# knife.net
KiCad netlist of a schematic drawn in EAGLE
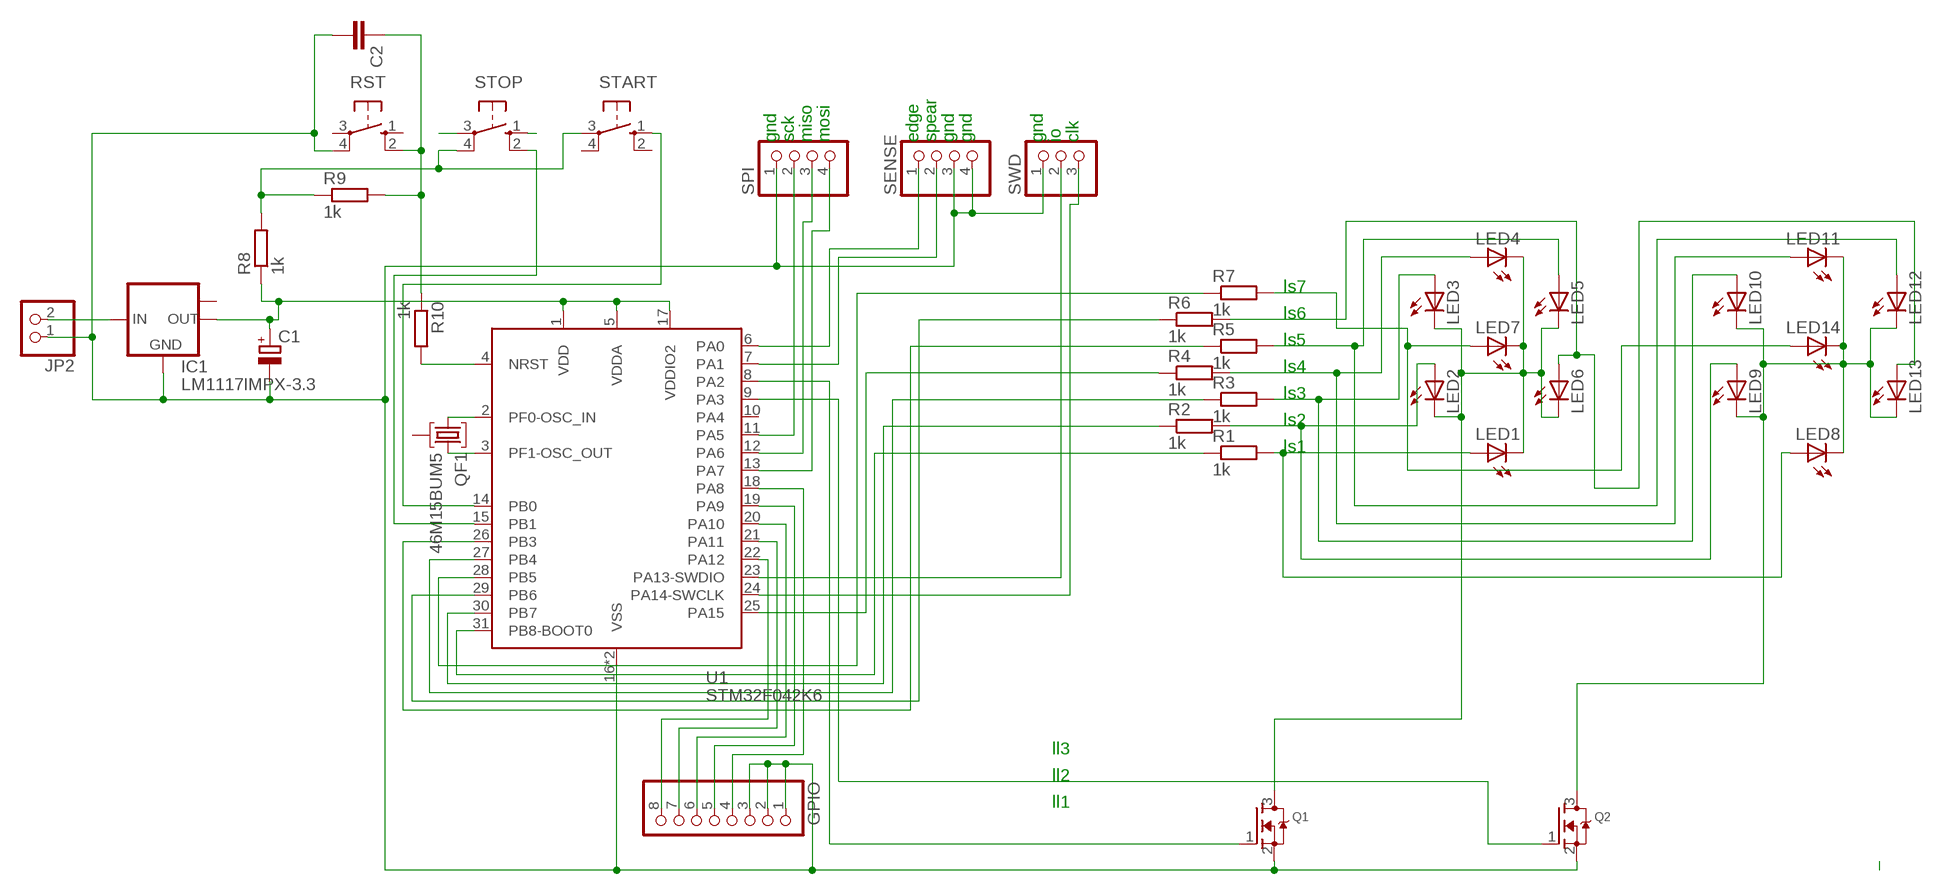
[diagram p0: schematic, sheet 1]

(export (version "E")
  (design (tool "Eeschema 10.0.6"))
  (components
    (comp (ref "C1")
      (value "CPOL-EUSMCD")
      (footprint "eagle-import:SMC_D")
      (libsource (lib "eagle-import") (part "CPOL-EUSMCD"))
    )
    (comp (ref "C2")
      (value "C-EUC1206")
      (footprint "eagle-import:C1206")
      (libsource (lib "eagle-import") (part "C-EUC1206"))
    )
    (comp (ref "GPIO")
      (value "PINHD-1X8")
      (footprint "eagle-import:1X08")
      (libsource (lib "eagle-import") (part "PINHD-1X8"))
    )
    (comp (ref "IC1")
      (value "LM1117IMPX-3.3")
      (footprint "eagle-import:SOT223")
      (libsource (lib "eagle-import") (part "LM1117IMPX-3.3"))
    )
    (comp (ref "JP2")
      (value "PINHD-1X2")
      (footprint "eagle-import:1X02")
      (libsource (lib "eagle-import") (part "PINHD-1X2"))
    )
    (comp (ref "LED1")
      (value "LEDSQR2X5")
      (footprint "eagle-import:LED2X5")
      (libsource (lib "eagle-import") (part "LEDSQR2X5"))
    )
    (comp (ref "LED2")
      (value "LEDSQR2X5")
      (footprint "eagle-import:LED2X5")
      (libsource (lib "eagle-import") (part "LEDSQR2X5"))
    )
    (comp (ref "LED3")
      (value "LEDSQR2X5")
      (footprint "eagle-import:LED2X5")
      (libsource (lib "eagle-import") (part "LEDSQR2X5"))
    )
    (comp (ref "LED4")
      (value "LEDSQR2X5")
      (footprint "eagle-import:LED2X5")
      (libsource (lib "eagle-import") (part "LEDSQR2X5"))
    )
    (comp (ref "LED5")
      (value "LEDSQR2X5")
      (footprint "eagle-import:LED2X5")
      (libsource (lib "eagle-import") (part "LEDSQR2X5"))
    )
    (comp (ref "LED6")
      (value "LEDSQR2X5")
      (footprint "eagle-import:LED2X5")
      (libsource (lib "eagle-import") (part "LEDSQR2X5"))
    )
    (comp (ref "LED7")
      (value "LEDSQR2X5")
      (footprint "eagle-import:LED2X5")
      (libsource (lib "eagle-import") (part "LEDSQR2X5"))
    )
    (comp (ref "LED8")
      (value "LEDSQR2X5")
      (footprint "eagle-import:LED2X5")
      (libsource (lib "eagle-import") (part "LEDSQR2X5"))
    )
    (comp (ref "LED9")
      (value "LEDSQR2X5")
      (footprint "eagle-import:LED2X5")
      (libsource (lib "eagle-import") (part "LEDSQR2X5"))
    )
    (comp (ref "LED10")
      (value "LEDSQR2X5")
      (footprint "eagle-import:LED2X5")
      (libsource (lib "eagle-import") (part "LEDSQR2X5"))
    )
    (comp (ref "LED11")
      (value "LEDSQR2X5")
      (footprint "eagle-import:LED2X5")
      (libsource (lib "eagle-import") (part "LEDSQR2X5"))
    )
    (comp (ref "LED12")
      (value "LEDSQR2X5")
      (footprint "eagle-import:LED2X5")
      (libsource (lib "eagle-import") (part "LEDSQR2X5"))
    )
    (comp (ref "LED13")
      (value "LEDSQR2X5")
      (footprint "eagle-import:LED2X5")
      (libsource (lib "eagle-import") (part "LEDSQR2X5"))
    )
    (comp (ref "LED14")
      (value "LEDSQR2X5")
      (footprint "eagle-import:LED2X5")
      (libsource (lib "eagle-import") (part "LEDSQR2X5"))
    )
    (comp (ref "Q1")
      (value "MOSFET-NREFLOW")
      (footprint "eagle-import:SOT23")
      (libsource (lib "eagle-import") (part "MOSFET-NREFLOW"))
    )
    (comp (ref "Q2")
      (value "MOSFET-NREFLOW")
      (footprint "eagle-import:SOT23")
      (libsource (lib "eagle-import") (part "MOSFET-NREFLOW"))
    )
    (comp (ref "QF1")
      (value "46M15BUM5")
      (footprint "eagle-import:UM5")
      (libsource (lib "eagle-import") (part "46M15BUM5"))
    )
    (comp (ref "R1")
      (value "1k")
      (footprint "eagle-import:R0805")
      (libsource (lib "eagle-import") (part "resistor_R-EU_R0805"))
    )
    (comp (ref "R2")
      (value "1k")
      (footprint "eagle-import:R0805")
      (libsource (lib "eagle-import") (part "resistor_R-EU_R0805"))
    )
    (comp (ref "R3")
      (value "1k")
      (footprint "eagle-import:R0805")
      (libsource (lib "eagle-import") (part "resistor_R-EU_R0805"))
    )
    (comp (ref "R4")
      (value "1k")
      (footprint "eagle-import:R0805")
      (libsource (lib "eagle-import") (part "resistor_R-EU_R0805"))
    )
    (comp (ref "R5")
      (value "1k")
      (footprint "eagle-import:R0805")
      (libsource (lib "eagle-import") (part "resistor_R-EU_R0805"))
    )
    (comp (ref "R6")
      (value "1k")
      (footprint "eagle-import:R0805")
      (libsource (lib "eagle-import") (part "resistor_R-EU_R0805"))
    )
    (comp (ref "R7")
      (value "1k")
      (footprint "eagle-import:R0805")
      (libsource (lib "eagle-import") (part "resistor_R-EU_R0805"))
    )
    (comp (ref "R8")
      (value "1k")
      (footprint "eagle-import:R1206")
      (libsource (lib "eagle-import") (part "R-EU_R1206"))
    )
    (comp (ref "R9")
      (value "1k")
      (footprint "eagle-import:R1206")
      (libsource (lib "eagle-import") (part "R-EU_R1206"))
    )
    (comp (ref "R10")
      (value "1k")
      (footprint "eagle-import:R1206")
      (libsource (lib "eagle-import") (part "R-EU_R1206"))
    )
    (comp (ref "RST")
      (value "10-XX")
      (footprint "eagle-import:B3F-10XX")
      (fields (field (name "MPN") "B3F-1000"))
      (libsource (lib "eagle-import") (part "10-XX"))
    )
    (comp (ref "SENSE")
      (value "PINHD-1X4")
      (footprint "eagle-import:1X04")
      (libsource (lib "eagle-import") (part "PINHD-1X4"))
    )
    (comp (ref "SPI")
      (value "PINHD-1X4")
      (footprint "eagle-import:1X04")
      (libsource (lib "eagle-import") (part "PINHD-1X4"))
    )
    (comp (ref "START")
      (value "10-XX")
      (footprint "eagle-import:B3F-10XX")
      (fields (field (name "MPN") "B3F-1000"))
      (libsource (lib "eagle-import") (part "10-XX"))
    )
    (comp (ref "STOP")
      (value "10-XX")
      (footprint "eagle-import:B3F-10XX")
      (fields (field (name "MPN") "B3F-1000"))
      (libsource (lib "eagle-import") (part "10-XX"))
    )
    (comp (ref "SWD")
      (value "PINHD-1X3")
      (footprint "eagle-import:1X03")
      (libsource (lib "eagle-import") (part "PINHD-1X3"))
    )
    (comp (ref "U1")
      (value "STM32F042K6")
      (footprint "eagle-import:QFP32-7X7")
      (libsource (lib "eagle-import") (part "STM32F042K6"))
    )
  )
  (nets
    (net (code "1") (name "Net-(IC1-GND)") (class "Default")
      (node (ref "C1") (pin "-") (pinfunction "-_-") (pintype "passive"))
      (node (ref "C2") (pin "2") (pinfunction "2_2") (pintype "passive"))
      (node (ref "GPIO") (pin "1") (pinfunction "1_1") (pintype "passive"))
      (node (ref "GPIO") (pin "2") (pinfunction "2_2") (pintype "passive"))
      (node (ref "GPIO") (pin "3") (pinfunction "3_3") (pintype "passive"))
      (node (ref "IC1") (pin "1") (pinfunction "GND_1") (pintype "input"))
      (node (ref "JP2") (pin "1") (pinfunction "1_1") (pintype "passive"))
      (node (ref "Q1") (pin "2") (pinfunction "S_2") (pintype "bidirectional"))
      (node (ref "Q2") (pin "2") (pinfunction "S_2") (pintype "bidirectional"))
      (node (ref "RST") (pin "4") (pinfunction "P1_4") (pintype "passive"))
      (node (ref "SENSE") (pin "3") (pinfunction "3_3") (pintype "passive"))
      (node (ref "SENSE") (pin "4") (pinfunction "4_4") (pintype "passive"))
      (node (ref "SPI") (pin "1") (pinfunction "1_1") (pintype "passive"))
      (node (ref "SWD") (pin "1") (pinfunction "1_1") (pintype "passive"))
      (node (ref "U1") (pin "16") (pinfunction "VSS_16") (pintype "power_in"))
      (node (ref "U1") (pin "32") (pinfunction "VSS_32") (pintype "power_in"))
    )
    (net (code "2") (name "Net-(IC1-IN)") (class "Default")
      (node (ref "IC1") (pin "3") (pinfunction "IN_3") (pintype "input"))
      (node (ref "JP2") (pin "2") (pinfunction "2_2") (pintype "passive"))
    )
    (net (code "3") (name "Net-(IC1-OUT)") (class "Default")
      (node (ref "C1") (pin "+") (pinfunction "+_+") (pintype "passive"))
      (node (ref "IC1") (pin "2") (pinfunction "OUT_2") (pintype "passive"))
      (node (ref "R8") (pin "1") (pinfunction "1_1") (pintype "passive"))
      (node (ref "U1") (pin "1") (pinfunction "VDD_1") (pintype "power_in"))
      (node (ref "U1") (pin "17") (pinfunction "VDDIO2_17") (pintype "power_in"))
      (node (ref "U1") (pin "5") (pinfunction "VDDA_5") (pintype "power_in"))
    )
    (net (code "4") (name "Net-(LED1-C)") (class "Default")
      (node (ref "LED1") (pin "K") (pinfunction "C_K") (pintype "passive"))
      (node (ref "LED2") (pin "K") (pinfunction "C_K") (pintype "passive"))
      (node (ref "LED3") (pin "K") (pinfunction "C_K") (pintype "passive"))
      (node (ref "LED4") (pin "K") (pinfunction "C_K") (pintype "passive"))
      (node (ref "LED5") (pin "K") (pinfunction "C_K") (pintype "passive"))
      (node (ref "LED6") (pin "K") (pinfunction "C_K") (pintype "passive"))
      (node (ref "LED7") (pin "K") (pinfunction "C_K") (pintype "passive"))
      (node (ref "Q1") (pin "3") (pinfunction "D_3") (pintype "bidirectional"))
    )
    (net (code "5") (name "Net-(LED1-PadA)") (class "Default")
      (node (ref "LED1") (pin "A") (pinfunction "A_A") (pintype "passive"))
      (node (ref "LED8") (pin "A") (pinfunction "A_A") (pintype "passive"))
      (node (ref "R1") (pin "2") (pinfunction "2_2") (pintype "passive"))
    )
    (net (code "6") (name "Net-(LED2-PadA)") (class "Default")
      (node (ref "LED2") (pin "A") (pinfunction "A_A") (pintype "passive"))
      (node (ref "LED9") (pin "A") (pinfunction "A_A") (pintype "passive"))
      (node (ref "R2") (pin "2") (pinfunction "2_2") (pintype "passive"))
    )
    (net (code "7") (name "Net-(LED10-C)") (class "Default")
      (node (ref "LED10") (pin "K") (pinfunction "C_K") (pintype "passive"))
      (node (ref "LED11") (pin "K") (pinfunction "C_K") (pintype "passive"))
      (node (ref "LED12") (pin "K") (pinfunction "C_K") (pintype "passive"))
      (node (ref "LED13") (pin "K") (pinfunction "C_K") (pintype "passive"))
      (node (ref "LED14") (pin "K") (pinfunction "C_K") (pintype "passive"))
      (node (ref "LED8") (pin "K") (pinfunction "C_K") (pintype "passive"))
      (node (ref "LED9") (pin "K") (pinfunction "C_K") (pintype "passive"))
      (node (ref "Q2") (pin "3") (pinfunction "D_3") (pintype "bidirectional"))
    )
    (net (code "8") (name "Net-(LED10-PadA)") (class "Default")
      (node (ref "LED10") (pin "A") (pinfunction "A_A") (pintype "passive"))
      (node (ref "LED3") (pin "A") (pinfunction "A_A") (pintype "passive"))
      (node (ref "R3") (pin "2") (pinfunction "2_2") (pintype "passive"))
    )
    (net (code "9") (name "Net-(LED11-PadA)") (class "Default")
      (node (ref "LED11") (pin "A") (pinfunction "A_A") (pintype "passive"))
      (node (ref "LED4") (pin "A") (pinfunction "A_A") (pintype "passive"))
      (node (ref "R4") (pin "2") (pinfunction "2_2") (pintype "passive"))
    )
    (net (code "10") (name "Net-(LED12-PadA)") (class "Default")
      (node (ref "LED12") (pin "A") (pinfunction "A_A") (pintype "passive"))
      (node (ref "LED5") (pin "A") (pinfunction "A_A") (pintype "passive"))
      (node (ref "R5") (pin "2") (pinfunction "2_2") (pintype "passive"))
    )
    (net (code "11") (name "Net-(LED13-PadA)") (class "Default")
      (node (ref "LED13") (pin "A") (pinfunction "A_A") (pintype "passive"))
      (node (ref "LED6") (pin "A") (pinfunction "A_A") (pintype "passive"))
      (node (ref "R6") (pin "2") (pinfunction "2_2") (pintype "passive"))
    )
    (net (code "12") (name "Net-(LED14-PadA)") (class "Default")
      (node (ref "LED14") (pin "A") (pinfunction "A_A") (pintype "passive"))
      (node (ref "LED7") (pin "A") (pinfunction "A_A") (pintype "passive"))
      (node (ref "R7") (pin "2") (pinfunction "2_2") (pintype "passive"))
    )
    (net (code "13") (name "Net-(Q1-G)") (class "Default")
      (node (ref "Q1") (pin "1") (pinfunction "G_1") (pintype "bidirectional"))
      (node (ref "U1") (pin "8") (pinfunction "PA2_8") (pintype "bidirectional"))
    )
    (net (code "14") (name "Net-(Q2-G)") (class "Default")
      (node (ref "Q2") (pin "1") (pinfunction "G_1") (pintype "bidirectional"))
      (node (ref "U1") (pin "9") (pinfunction "PA3_9") (pintype "bidirectional"))
    )
    (net (code "15") (name "Net-(RST-S1)") (class "Default")
      (node (ref "C2") (pin "1") (pinfunction "1_1") (pintype "passive"))
      (node (ref "R10") (pin "1") (pinfunction "1_1") (pintype "passive"))
      (node (ref "R9") (pin "2") (pinfunction "2_2") (pintype "passive"))
      (node (ref "RST") (pin "2") (pinfunction "S1_2") (pintype "passive"))
    )
    (net (code "16") (name "Net-(START-P)") (class "Default")
      (node (ref "R8") (pin "2") (pinfunction "2_2") (pintype "passive"))
      (node (ref "R9") (pin "1") (pinfunction "1_1") (pintype "passive"))
      (node (ref "START") (pin "3") (pinfunction "P_3") (pintype "passive"))
      (node (ref "STOP") (pin "4") (pinfunction "P1_4") (pintype "passive"))
    )
    (net (code "17") (name "Net-(START-S)") (class "Default")
      (node (ref "START") (pin "1") (pinfunction "S_1") (pintype "passive"))
      (node (ref "U1") (pin "14") (pinfunction "PB0_14") (pintype "bidirectional"))
    )
    (net (code "18") (name "Net-(STOP-S1)") (class "Default")
      (node (ref "STOP") (pin "2") (pinfunction "S1_2") (pintype "passive"))
      (node (ref "U1") (pin "15") (pinfunction "PB1_15") (pintype "bidirectional"))
    )
    (net (code "19") (name "Net-(U1-NRST)") (class "Default")
      (node (ref "R10") (pin "2") (pinfunction "2_2") (pintype "passive"))
      (node (ref "U1") (pin "4") (pinfunction "NRST_4") (pintype "bidirectional"))
    )
    (net (code "20") (name "Net-(U1-PA0)") (class "Default")
      (node (ref "SENSE") (pin "1") (pinfunction "1_1") (pintype "passive"))
      (node (ref "U1") (pin "6") (pinfunction "PA0_6") (pintype "bidirectional"))
    )
    (net (code "21") (name "Net-(U1-PA1)") (class "Default")
      (node (ref "SENSE") (pin "2") (pinfunction "2_2") (pintype "passive"))
      (node (ref "U1") (pin "7") (pinfunction "PA1_7") (pintype "bidirectional"))
    )
    (net (code "22") (name "Net-(U1-PA5)") (class "Default")
      (node (ref "SPI") (pin "2") (pinfunction "2_2") (pintype "passive"))
      (node (ref "U1") (pin "11") (pinfunction "PA5_11") (pintype "bidirectional"))
    )
    (net (code "23") (name "Net-(U1-PA6)") (class "Default")
      (node (ref "SPI") (pin "3") (pinfunction "3_3") (pintype "passive"))
      (node (ref "U1") (pin "12") (pinfunction "PA6_12") (pintype "bidirectional"))
    )
    (net (code "24") (name "Net-(U1-PA7)") (class "Default")
      (node (ref "SPI") (pin "4") (pinfunction "4_4") (pintype "passive"))
      (node (ref "U1") (pin "13") (pinfunction "PA7_13") (pintype "bidirectional"))
    )
    (net (code "25") (name "Net-(U1-PA8)") (class "Default")
      (node (ref "GPIO") (pin "4") (pinfunction "4_4") (pintype "passive"))
      (node (ref "U1") (pin "18") (pinfunction "PA8_18") (pintype "bidirectional"))
    )
    (net (code "26") (name "Net-(U1-PA9)") (class "Default")
      (node (ref "GPIO") (pin "5") (pinfunction "5_5") (pintype "passive"))
      (node (ref "U1") (pin "19") (pinfunction "PA9_19") (pintype "bidirectional"))
    )
    (net (code "27") (name "Net-(U1-PA10)") (class "Default")
      (node (ref "GPIO") (pin "6") (pinfunction "6_6") (pintype "passive"))
      (node (ref "U1") (pin "20") (pinfunction "PA10_20") (pintype "bidirectional"))
    )
    (net (code "28") (name "Net-(U1-PA11)") (class "Default")
      (node (ref "GPIO") (pin "7") (pinfunction "7_7") (pintype "passive"))
      (node (ref "U1") (pin "21") (pinfunction "PA11_21") (pintype "bidirectional"))
    )
    (net (code "29") (name "Net-(U1-PA12)") (class "Default")
      (node (ref "GPIO") (pin "8") (pinfunction "8_8") (pintype "passive"))
      (node (ref "U1") (pin "22") (pinfunction "PA12_22") (pintype "bidirectional"))
    )
    (net (code "30") (name "Net-(U1-PA13-SWDIO)") (class "Default")
      (node (ref "SWD") (pin "2") (pinfunction "2_2") (pintype "passive"))
      (node (ref "U1") (pin "23") (pinfunction "PA13-SWDIO_23") (pintype "bidirectional"))
    )
    (net (code "31") (name "Net-(U1-PA14-SWCLK)") (class "Default")
      (node (ref "SWD") (pin "3") (pinfunction "3_3") (pintype "passive"))
      (node (ref "U1") (pin "24") (pinfunction "PA14-SWCLK_24") (pintype "bidirectional"))
    )
    (net (code "32") (name "Net-(U1-PA15)") (class "Default")
      (node (ref "R4") (pin "1") (pinfunction "1_1") (pintype "passive"))
      (node (ref "U1") (pin "25") (pinfunction "PA15_25") (pintype "bidirectional"))
    )
    (net (code "33") (name "Net-(U1-PB3)") (class "Default")
      (node (ref "R5") (pin "1") (pinfunction "1_1") (pintype "passive"))
      (node (ref "U1") (pin "26") (pinfunction "PB3_26") (pintype "bidirectional"))
    )
    (net (code "34") (name "Net-(U1-PB4)") (class "Default")
      (node (ref "R3") (pin "1") (pinfunction "1_1") (pintype "passive"))
      (node (ref "U1") (pin "27") (pinfunction "PB4_27") (pintype "bidirectional"))
    )
    (net (code "35") (name "Net-(U1-PB5)") (class "Default")
      (node (ref "R7") (pin "1") (pinfunction "1_1") (pintype "passive"))
      (node (ref "U1") (pin "28") (pinfunction "PB5_28") (pintype "bidirectional"))
    )
    (net (code "36") (name "Net-(U1-PB6)") (class "Default")
      (node (ref "R6") (pin "1") (pinfunction "1_1") (pintype "passive"))
      (node (ref "U1") (pin "29") (pinfunction "PB6_29") (pintype "bidirectional"))
    )
    (net (code "37") (name "Net-(U1-PB7)") (class "Default")
      (node (ref "R2") (pin "1") (pinfunction "1_1") (pintype "passive"))
      (node (ref "U1") (pin "30") (pinfunction "PB7_30") (pintype "bidirectional"))
    )
    (net (code "38") (name "Net-(U1-PB8-BOOT0)") (class "Default")
      (node (ref "R1") (pin "1") (pinfunction "1_1") (pintype "passive"))
      (node (ref "U1") (pin "31") (pinfunction "PB8-BOOT0_31") (pintype "bidirectional"))
    )
    (net (code "39") (name "Net-(U1-PF0-OSC_IN)") (class "Default")
      (node (ref "QF1") (pin "1") (pinfunction "1_1") (pintype "passive"))
      (node (ref "U1") (pin "2") (pinfunction "PF0-OSC_IN_2") (pintype "bidirectional"))
    )
    (net (code "40") (name "Net-(U1-PF1-OSC_OUT)") (class "Default")
      (node (ref "QF1") (pin "3") (pinfunction "3_3") (pintype "passive"))
      (node (ref "U1") (pin "3") (pinfunction "PF1-OSC_OUT_3") (pintype "bidirectional"))
    )
    (net (code "41") (name "unconnected-(IC1-OUT1-PadTAB)") (class "Default")
      (node (ref "IC1") (pin "TAB") (pinfunction "OUT1_TAB") (pintype "passive"))
    )
    (net (code "42") (name "unconnected-(QF1-Pad2)") (class "Default")
      (node (ref "QF1") (pin "2") (pinfunction "2_2") (pintype "passive"))
    )
    (net (code "43") (name "unconnected-(RST-P-Pad3)") (class "Default")
      (node (ref "RST") (pin "3") (pinfunction "P_3") (pintype "passive"))
    )
    (net (code "44") (name "unconnected-(RST-S-Pad1)") (class "Default")
      (node (ref "RST") (pin "1") (pinfunction "S_1") (pintype "passive"))
    )
    (net (code "45") (name "unconnected-(START-P1-Pad4)") (class "Default")
      (node (ref "START") (pin "4") (pinfunction "P1_4") (pintype "passive"))
    )
    (net (code "46") (name "unconnected-(START-S1-Pad2)") (class "Default")
      (node (ref "START") (pin "2") (pinfunction "S1_2") (pintype "passive"))
    )
    (net (code "47") (name "unconnected-(STOP-P-Pad3)") (class "Default")
      (node (ref "STOP") (pin "3") (pinfunction "P_3") (pintype "passive"))
    )
    (net (code "48") (name "unconnected-(STOP-S-Pad1)") (class "Default")
      (node (ref "STOP") (pin "1") (pinfunction "S_1") (pintype "passive"))
    )
    (net (code "49") (name "unconnected-(U1-PA4-Pad10)") (class "Default")
      (node (ref "U1") (pin "10") (pinfunction "PA4_10") (pintype "bidirectional"))
    )
  )
)
